# ESP32-PICO-MINI-02.net
KiCad netlist of a schematic drawn in Altium Designer
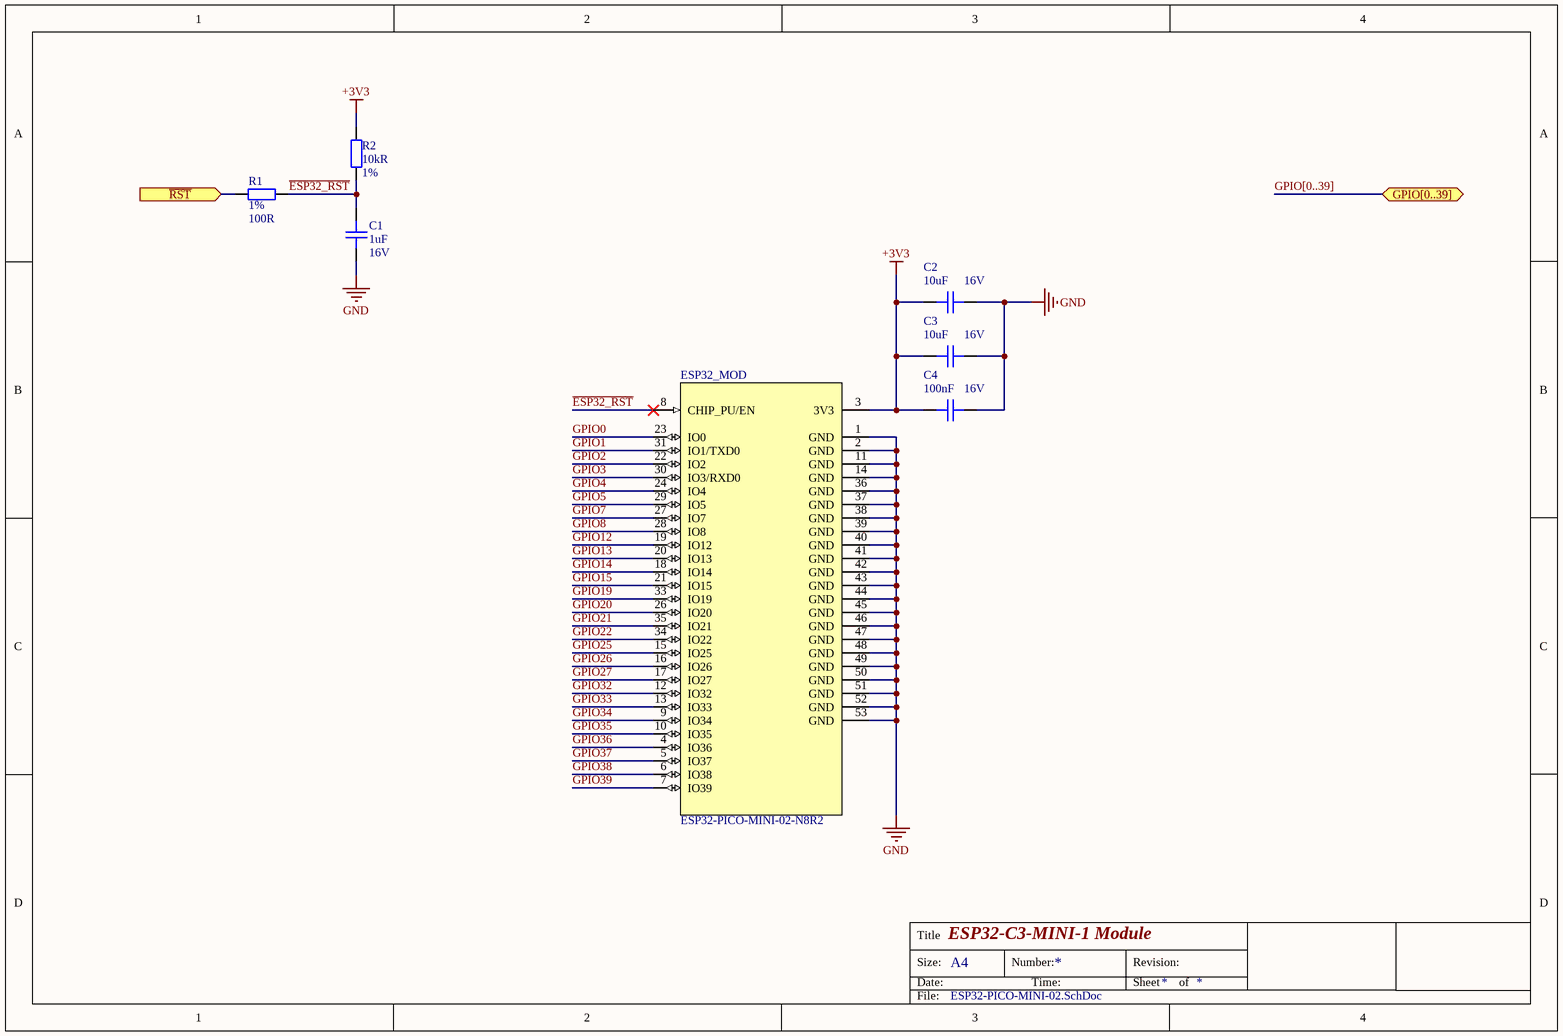
[diagram p0: ESP32-PICO-MINI-02.SchDoc]

(export (version "E")
  (design (tool "Eeschema 10.0.6"))
  (components
    (comp (ref "C1")
      (value "CAP CER 1UF 16V X5R 0402")
      (footprint "C0402")
      (description "1µF ±10% 16V Ceramic Capacitor X5R 0402 (1005 Metric)")
      (fields
        (field (name "MANUFACTURER PART NUMBER") "CC0402KRX5R7BB105")
        (field (name "MANUFACTURER") "Yageo")
        (field (name "CAPACITANCE") "1uF")
        (field (name "VOLTAGE RATING") "16V")
      )
      (libsource (lib "capacitors_smd") (part "CAP CER 1UF 16V X5R 0402"))
    )
    (comp (ref "C2")
      (value "CAP CER 10UF 16V X5R 0603")
      (footprint "C0603")
      (description "10µF ±10% 16V Ceramic Capacitor X5R 0603 (1608 Metric)")
      (fields
        (field (name "MANUFACTURER") "Murata")
        (field (name "MANUFACTURER PART NUMBER") "GRM188R61C106KAALJ")
        (field (name "CAPACITANCE") "10uF")
        (field (name "VOLTAGE RATING") "16V")
      )
      (libsource (lib "capacitors_smd") (part "CAP CER 10UF 16V X5R 0603"))
    )
    (comp (ref "C3")
      (value "CAP CER 10UF 16V X5R 0603")
      (footprint "C0603")
      (description "10µF ±10% 16V Ceramic Capacitor X5R 0603 (1608 Metric)")
      (fields
        (field (name "MANUFACTURER") "Murata")
        (field (name "MANUFACTURER PART NUMBER") "GRM188R61C106KAALJ")
        (field (name "CAPACITANCE") "10uF")
        (field (name "VOLTAGE RATING") "16V")
      )
      (libsource (lib "capacitors_smd") (part "CAP CER 10UF 16V X5R 0603"))
    )
    (comp (ref "C4")
      (value "CAP CER 0.1UF 16V X7R 0402")
      (footprint "C0402")
      (description "0.1µF ±10% 16V Ceramic Capacitor X7R 0402 (1005 Metric)")
      (fields
        (field (name "MANUFACTURER PART NUMBER") "CC0402KRX7R7BB104")
        (field (name "MANUFACTURER") "Yageo")
        (field (name "CAPACITANCE") "100nF")
        (field (name "VOLTAGE") "16V")
      )
      (libsource (lib "capacitors_smd") (part "CAP CER 0.1UF 16V X7R 0402"))
    )
    (comp (ref "ESP32_MOD")
      (value "ESP32-PICO-MINI-02-N8R2")
      (footprint "MODULE_ESP32-C3-MINI-1")
      (fields (field (name "MANUFACTURER") "Espressif Systems"))
      (libsource (lib "Control_Board_Model") (part "MOD ESP32-PICO-MINI-02-N8R2, PCB ANT"))
    )
    (comp (ref "R1")
      (value "RES SMD 100 OHM 1% 1/16W 0402")
      (footprint "R0402")
      (description "100 Ohms ±1% 0.063W, 1/16W Chip Resistor 0402 (1005 Metric) Moisture Resistant Thick Film")
      (fields
        (field (name "MANUFACTURER PART NUMBER") "RC0402FR-07100RL")
        (field (name "MANUFACTURER") "Yageo")
        (field (name "TOLERANCE") "1%")
        (field (name "RESISTANCE") "100R")
      )
      (libsource (lib "resistors_smd") (part "RES SMD 100 OHM 1% 1/16W 0402"))
    )
    (comp (ref "R2")
      (value "RES SMD 10K OHM 1% 1/16W 0402")
      (footprint "R0402")
      (description "10 kOhms ±1% 0.063W, 1/16W Chip Resistor 0402 (1005 Metric) Moisture Resistant Thick Film")
      (fields
        (field (name "MANUFACTURER PART NUMBER") "RC0402FR-0710KP")
        (field (name "MANUFACTURER") "Yageo")
        (field (name "RESISTANCE") "10kR")
        (field (name "TOLERANCE") "1%")
      )
      (libsource (lib "resistors_smd") (part "RES SMD 10K OHM 1% 1/16W 0402"))
    )
  )
  (nets
    (net (code "14") (name "+3V3") (class "Default")
      (node (ref "C2") (pin "2") (pinfunction "2_2") (pintype "passive"))
      (node (ref "C3") (pin "2") (pinfunction "2_2") (pintype "passive"))
      (node (ref "C4") (pin "2") (pinfunction "2_2") (pintype "passive"))
      (node (ref "ESP32_MOD") (pin "3") (pinfunction "3V3_3") (pintype "power_in"))
      (node (ref "R2") (pin "1") (pinfunction "1_1") (pintype "passive"))
    )
    (net (code "15") (name "/ESP32_RST") (class "Default")
      (node (ref "C1") (pin "2") (pinfunction "2_2") (pintype "passive"))
      (node (ref "ESP32_MOD") (pin "8") (pinfunction "CHIP_PU/EN_8") (pintype "input"))
      (node (ref "R1") (pin "1") (pinfunction "1_1") (pintype "passive"))
      (node (ref "R2") (pin "2") (pinfunction "2_2") (pintype "passive"))
    )
    (net (code "16") (name "/GPIO0") (class "Default")
      (node (ref "ESP32_MOD") (pin "23") (pinfunction "IO0_23") (pintype "bidirectional"))
    )
    (net (code "17") (name "/GPIO1") (class "Default")
      (node (ref "ESP32_MOD") (pin "31") (pinfunction "IO1/TXD0_31") (pintype "bidirectional"))
    )
    (net (code "18") (name "/GPIO2") (class "Default")
      (node (ref "ESP32_MOD") (pin "22") (pinfunction "IO2_22") (pintype "bidirectional"))
    )
    (net (code "19") (name "/GPIO3") (class "Default")
      (node (ref "ESP32_MOD") (pin "30") (pinfunction "IO3/RXD0_30") (pintype "bidirectional"))
    )
    (net (code "20") (name "/GPIO4") (class "Default")
      (node (ref "ESP32_MOD") (pin "24") (pinfunction "IO4_24") (pintype "bidirectional"))
    )
    (net (code "21") (name "/GPIO5") (class "Default")
      (node (ref "ESP32_MOD") (pin "29") (pinfunction "IO5_29") (pintype "bidirectional"))
    )
    (net (code "22") (name "/GPIO7") (class "Default")
      (node (ref "ESP32_MOD") (pin "27") (pinfunction "IO7_27") (pintype "bidirectional"))
    )
    (net (code "23") (name "/GPIO8") (class "Default")
      (node (ref "ESP32_MOD") (pin "28") (pinfunction "IO8_28") (pintype "bidirectional"))
    )
    (net (code "24") (name "/GPIO12") (class "Default")
      (node (ref "ESP32_MOD") (pin "19") (pinfunction "IO12_19") (pintype "bidirectional"))
    )
    (net (code "25") (name "/GPIO13") (class "Default")
      (node (ref "ESP32_MOD") (pin "20") (pinfunction "IO13_20") (pintype "bidirectional"))
    )
    (net (code "26") (name "/GPIO14") (class "Default")
      (node (ref "ESP32_MOD") (pin "18") (pinfunction "IO14_18") (pintype "bidirectional"))
    )
    (net (code "27") (name "/GPIO15") (class "Default")
      (node (ref "ESP32_MOD") (pin "21") (pinfunction "IO15_21") (pintype "bidirectional"))
    )
    (net (code "28") (name "/GPIO19") (class "Default")
      (node (ref "ESP32_MOD") (pin "33") (pinfunction "IO19_33") (pintype "bidirectional"))
    )
    (net (code "29") (name "/GPIO20") (class "Default")
      (node (ref "ESP32_MOD") (pin "26") (pinfunction "IO20_26") (pintype "bidirectional"))
    )
    (net (code "30") (name "/GPIO21") (class "Default")
      (node (ref "ESP32_MOD") (pin "35") (pinfunction "IO21_35") (pintype "bidirectional"))
    )
    (net (code "31") (name "/GPIO22") (class "Default")
      (node (ref "ESP32_MOD") (pin "34") (pinfunction "IO22_34") (pintype "bidirectional"))
    )
    (net (code "32") (name "/GPIO25") (class "Default")
      (node (ref "ESP32_MOD") (pin "15") (pinfunction "IO25_15") (pintype "bidirectional"))
    )
    (net (code "33") (name "/GPIO26") (class "Default")
      (node (ref "ESP32_MOD") (pin "16") (pinfunction "IO26_16") (pintype "bidirectional"))
    )
    (net (code "34") (name "/GPIO27") (class "Default")
      (node (ref "ESP32_MOD") (pin "17") (pinfunction "IO27_17") (pintype "bidirectional"))
    )
    (net (code "35") (name "/GPIO32") (class "Default")
      (node (ref "ESP32_MOD") (pin "12") (pinfunction "IO32_12") (pintype "bidirectional"))
    )
    (net (code "36") (name "/GPIO33") (class "Default")
      (node (ref "ESP32_MOD") (pin "13") (pinfunction "IO33_13") (pintype "bidirectional"))
    )
    (net (code "37") (name "/GPIO34") (class "Default")
      (node (ref "ESP32_MOD") (pin "9") (pinfunction "IO34_9") (pintype "bidirectional"))
    )
    (net (code "38") (name "/GPIO35") (class "Default")
      (node (ref "ESP32_MOD") (pin "10") (pinfunction "IO35_10") (pintype "bidirectional"))
    )
    (net (code "39") (name "/GPIO36") (class "Default")
      (node (ref "ESP32_MOD") (pin "4") (pinfunction "IO36_4") (pintype "bidirectional"))
    )
    (net (code "40") (name "/GPIO37") (class "Default")
      (node (ref "ESP32_MOD") (pin "5") (pinfunction "IO37_5") (pintype "bidirectional"))
    )
    (net (code "41") (name "/GPIO38") (class "Default")
      (node (ref "ESP32_MOD") (pin "6") (pinfunction "IO38_6") (pintype "bidirectional"))
    )
    (net (code "42") (name "/GPIO39") (class "Default")
      (node (ref "ESP32_MOD") (pin "7") (pinfunction "IO39_7") (pintype "bidirectional"))
    )
    (net (code "44") (name "/RST") (class "Default")
      (node (ref "R1") (pin "2") (pinfunction "2_2") (pintype "passive"))
    )
    (net (code "45") (name "GND") (class "Default")
      (node (ref "C1") (pin "1") (pinfunction "1_1") (pintype "passive"))
      (node (ref "C2") (pin "1") (pinfunction "1_1") (pintype "passive"))
      (node (ref "C3") (pin "1") (pinfunction "1_1") (pintype "passive"))
      (node (ref "C4") (pin "1") (pinfunction "1_1") (pintype "passive"))
      (node (ref "ESP32_MOD") (pin "1") (pinfunction "GND_1") (pintype "power_in"))
      (node (ref "ESP32_MOD") (pin "11") (pinfunction "GND_11") (pintype "power_in"))
      (node (ref "ESP32_MOD") (pin "14") (pinfunction "GND_14") (pintype "power_in"))
      (node (ref "ESP32_MOD") (pin "2") (pinfunction "GND_2") (pintype "power_in"))
      (node (ref "ESP32_MOD") (pin "36") (pinfunction "GND_36") (pintype "power_in"))
      (node (ref "ESP32_MOD") (pin "37") (pinfunction "GND_37") (pintype "power_in"))
      (node (ref "ESP32_MOD") (pin "38") (pinfunction "GND_38") (pintype "power_in"))
      (node (ref "ESP32_MOD") (pin "39") (pinfunction "GND_39") (pintype "power_in"))
      (node (ref "ESP32_MOD") (pin "40") (pinfunction "GND_40") (pintype "power_in"))
      (node (ref "ESP32_MOD") (pin "41") (pinfunction "GND_41") (pintype "power_in"))
      (node (ref "ESP32_MOD") (pin "42") (pinfunction "GND_42") (pintype "power_in"))
      (node (ref "ESP32_MOD") (pin "43") (pinfunction "GND_43") (pintype "power_in"))
      (node (ref "ESP32_MOD") (pin "44") (pinfunction "GND_44") (pintype "power_in"))
      (node (ref "ESP32_MOD") (pin "45") (pinfunction "GND_45") (pintype "power_in"))
      (node (ref "ESP32_MOD") (pin "46") (pinfunction "GND_46") (pintype "power_in"))
      (node (ref "ESP32_MOD") (pin "47") (pinfunction "GND_47") (pintype "power_in"))
      (node (ref "ESP32_MOD") (pin "48") (pinfunction "GND_48") (pintype "power_in"))
      (node (ref "ESP32_MOD") (pin "49") (pinfunction "GND_49") (pintype "power_in"))
      (node (ref "ESP32_MOD") (pin "50") (pinfunction "GND_50") (pintype "power_in"))
      (node (ref "ESP32_MOD") (pin "51") (pinfunction "GND_51") (pintype "power_in"))
      (node (ref "ESP32_MOD") (pin "52") (pinfunction "GND_52") (pintype "power_in"))
      (node (ref "ESP32_MOD") (pin "53") (pinfunction "GND_53") (pintype "power_in"))
    )
    (net (code "46") (name "unconnected-(ESP32_MOD-NC-Pad4)") (class "Default")
      (node (ref "ESP32_MOD") (pin "4") (pinfunction "NC_4") (pintype "passive"))
    )
    (net (code "47") (name "unconnected-(ESP32_MOD-NC-Pad7)") (class "Default")
      (node (ref "ESP32_MOD") (pin "7") (pinfunction "NC_7") (pintype "passive"))
    )
    (net (code "48") (name "unconnected-(ESP32_MOD-NC-Pad9)") (class "Default")
      (node (ref "ESP32_MOD") (pin "9") (pinfunction "NC_9") (pintype "passive"))
    )
    (net (code "49") (name "unconnected-(ESP32_MOD-NC-Pad10)") (class "Default")
      (node (ref "ESP32_MOD") (pin "10") (pinfunction "NC_10") (pintype "passive"))
    )
    (net (code "50") (name "unconnected-(ESP32_MOD-NC-Pad15)") (class "Default")
      (node (ref "ESP32_MOD") (pin "15") (pinfunction "NC_15") (pintype "passive"))
    )
    (net (code "51") (name "unconnected-(ESP32_MOD-NC-Pad17)") (class "Default")
      (node (ref "ESP32_MOD") (pin "17") (pinfunction "NC_17") (pintype "passive"))
    )
    (net (code "52") (name "unconnected-(ESP32_MOD-NC-Pad24)") (class "Default")
      (node (ref "ESP32_MOD") (pin "24") (pinfunction "NC_24") (pintype "passive"))
    )
    (net (code "53") (name "unconnected-(ESP32_MOD-NC-Pad25)") (class "Default")
      (node (ref "ESP32_MOD") (pin "25") (pinfunction "NC_25") (pintype "passive"))
    )
    (net (code "54") (name "unconnected-(ESP32_MOD-NC-Pad28)") (class "Default")
      (node (ref "ESP32_MOD") (pin "28") (pinfunction "NC_28") (pintype "passive"))
    )
    (net (code "55") (name "unconnected-(ESP32_MOD-NC-Pad29)") (class "Default")
      (node (ref "ESP32_MOD") (pin "29") (pinfunction "NC_29") (pintype "passive"))
    )
    (net (code "56") (name "unconnected-(ESP32_MOD-NC-Pad32)") (class "Default")
      (node (ref "ESP32_MOD") (pin "32") (pinfunction "NC_32") (pintype "passive"))
    )
    (net (code "57") (name "unconnected-(ESP32_MOD-NC-Pad33)") (class "Default")
      (node (ref "ESP32_MOD") (pin "33") (pinfunction "NC_33") (pintype "passive"))
    )
    (net (code "58") (name "unconnected-(ESP32_MOD-NC-Pad34)") (class "Default")
      (node (ref "ESP32_MOD") (pin "34") (pinfunction "NC_34") (pintype "passive"))
    )
    (net (code "59") (name "unconnected-(ESP32_MOD-NC-Pad35)") (class "Default")
      (node (ref "ESP32_MOD") (pin "35") (pinfunction "NC_35") (pintype "passive"))
    )
  )
)
